# 02-DAC.net
KiCad netlist of a schematic drawn in Altium Designer
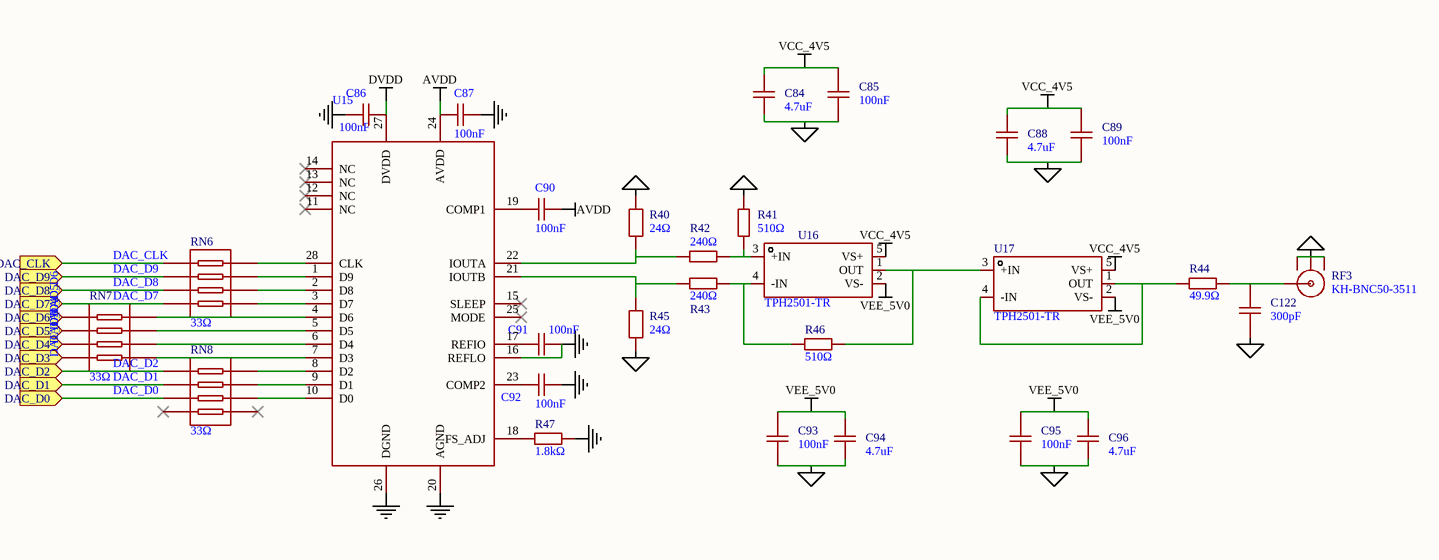
[diagram p0: 02-DAC.schdoc]

(export (version "E")
  (design (tool "Eeschema 10.0.6"))
  (components
    (comp (ref "C84")
      (value "4.7uF")
      (footprint "C0603")
      (fields
        (field (name "MANUFACTURER") "SAMSUNG(三星)")
        (field (name "MANUFACTURER PART") "CL10A475KO8NNNC")
        (field (name "TOLERANCE") "±10%")
      )
      (libsource (lib "altium-import") (part "root_1_CL10A475KO8NNNC_"))
    )
    (comp (ref "C85")
      (value "100nF")
      (footprint "C0603")
      (fields
        (field (name "MANUFACTURER") "HRE(芯声)")
        (field (name "MANUFACTURER PART") "CGA0603X7R104K500JT")
        (field (name "TOLERANCE") "±10%")
      )
      (libsource (lib "altium-import") (part "root_1_CGA0603X7R104K500JT_"))
    )
    (comp (ref "C86")
      (value "100nF")
      (footprint "C0603")
      (fields
        (field (name "MANUFACTURER") "HRE(芯声)")
        (field (name "MANUFACTURER PART") "CGA0603X7R104K500JT")
        (field (name "ALTIUM_VALUE") "100nF")
        (field (name "TOLERANCE") "±10%")
      )
      (libsource (lib "altium-import") (part "root_0_CGA0603X7R104K500JT_"))
    )
    (comp (ref "C87")
      (value "100nF")
      (footprint "C0603")
      (fields
        (field (name "MANUFACTURER") "HRE(芯声)")
        (field (name "MANUFACTURER PART") "CGA0603X7R104K500JT")
        (field (name "ALTIUM_VALUE") "100nF")
        (field (name "TOLERANCE") "±10%")
      )
      (libsource (lib "altium-import") (part "root_2_CGA0603X7R104K500JT_"))
    )
    (comp (ref "C88")
      (value "4.7uF")
      (footprint "C0603")
      (fields
        (field (name "MANUFACTURER") "SAMSUNG(三星)")
        (field (name "MANUFACTURER PART") "CL10A475KO8NNNC")
        (field (name "TOLERANCE") "±10%")
      )
      (libsource (lib "altium-import") (part "root_1_CL10A475KO8NNNC_"))
    )
    (comp (ref "C89")
      (value "100nF")
      (footprint "C0603")
      (fields
        (field (name "MANUFACTURER") "HRE(芯声)")
        (field (name "MANUFACTURER PART") "CGA0603X7R104K500JT")
        (field (name "TOLERANCE") "±10%")
      )
      (libsource (lib "altium-import") (part "root_1_CGA0603X7R104K500JT_"))
    )
    (comp (ref "C90")
      (value "100nF")
      (footprint "C0603")
      (fields
        (field (name "MANUFACTURER") "HRE(芯声)")
        (field (name "MANUFACTURER PART") "CGA0603X7R104K500JT")
        (field (name "ALTIUM_VALUE") "100nF")
        (field (name "TOLERANCE") "±10%")
      )
      (libsource (lib "altium-import") (part "root_2_CGA0603X7R104K500JT_"))
    )
    (comp (ref "C91")
      (value "100nF")
      (footprint "C0603")
      (fields
        (field (name "MANUFACTURER") "HRE(芯声)")
        (field (name "MANUFACTURER PART") "CGA0603X7R104K500JT")
        (field (name "ALTIUM_VALUE") "100nF")
        (field (name "TOLERANCE") "±10%")
      )
      (libsource (lib "altium-import") (part "root_2_CGA0603X7R104K500JT_"))
    )
    (comp (ref "C92")
      (value "100nF")
      (footprint "C0603")
      (fields
        (field (name "MANUFACTURER") "HRE(芯声)")
        (field (name "MANUFACTURER PART") "CGA0603X7R104K500JT")
        (field (name "ALTIUM_VALUE") "100nF")
        (field (name "TOLERANCE") "±10%")
      )
      (libsource (lib "altium-import") (part "root_2_CGA0603X7R104K500JT_"))
    )
    (comp (ref "C93")
      (value "100nF")
      (footprint "C0603")
      (fields
        (field (name "MANUFACTURER") "HRE(芯声)")
        (field (name "MANUFACTURER PART") "CGA0603X7R104K500JT")
        (field (name "TOLERANCE") "±10%")
      )
      (libsource (lib "altium-import") (part "root_1_CGA0603X7R104K500JT_"))
    )
    (comp (ref "C94")
      (value "4.7uF")
      (footprint "C0603")
      (fields
        (field (name "MANUFACTURER") "SAMSUNG(三星)")
        (field (name "MANUFACTURER PART") "CL10A475KO8NNNC")
        (field (name "TOLERANCE") "±10%")
      )
      (libsource (lib "altium-import") (part "root_1_CL10A475KO8NNNC_"))
    )
    (comp (ref "C95")
      (value "100nF")
      (footprint "C0603")
      (fields
        (field (name "MANUFACTURER") "HRE(芯声)")
        (field (name "MANUFACTURER PART") "CGA0603X7R104K500JT")
        (field (name "TOLERANCE") "±10%")
      )
      (libsource (lib "altium-import") (part "root_1_CGA0603X7R104K500JT_"))
    )
    (comp (ref "C96")
      (value "4.7uF")
      (footprint "C0603")
      (fields
        (field (name "MANUFACTURER") "SAMSUNG(三星)")
        (field (name "MANUFACTURER PART") "CL10A475KO8NNNC")
        (field (name "TOLERANCE") "±10%")
      )
      (libsource (lib "altium-import") (part "root_1_CL10A475KO8NNNC_"))
    )
    (comp (ref "C122")
      (value "300pF")
      (footprint "C0603")
      (fields
        (field (name "MANUFACTURER") "YAGEO(国巨)")
        (field (name "MANUFACTURER PART") "CC0603JRNPO9BN301")
        (field (name "TOLERANCE") "±5%")
      )
      (libsource (lib "altium-import") (part "root_1_CC0603JRNPO9BN301_"))
    )
    (comp (ref "R40")
      (value "24Ω")
      (footprint "R0603")
      (fields
        (field (name "MANUFACTURER") "FOJAN(富捷)")
        (field (name "MANUFACTURER PART") "FRC0603F24R0TS")
        (field (name "TOLERANCE") "±1%")
      )
      (libsource (lib "altium-import") (part "root_1_FRC0603F24R0TS_"))
    )
    (comp (ref "R41")
      (value "510Ω")
      (footprint "R0603")
      (fields
        (field (name "MANUFACTURER") "UNI-ROYAL(厚声)")
        (field (name "MANUFACTURER PART") "0603WAF5100T5E")
        (field (name "TOLERANCE") "±1%")
      )
      (libsource (lib "altium-import") (part "root_1_0603WAF5100T5E_"))
    )
    (comp (ref "R42")
      (value "240Ω")
      (footprint "R0603")
      (fields
        (field (name "MANUFACTURER") "UNI-ROYAL(厚声)")
        (field (name "MANUFACTURER PART") "0603WAF2400T5E")
        (field (name "TOLERANCE") "±1%")
      )
      (libsource (lib "altium-import") (part "root_0_0603WAF2400T5E_"))
    )
    (comp (ref "R43")
      (value "240Ω")
      (footprint "R0603")
      (fields
        (field (name "MANUFACTURER") "UNI-ROYAL(厚声)")
        (field (name "MANUFACTURER PART") "0603WAF2400T5E")
        (field (name "TOLERANCE") "±1%")
      )
      (libsource (lib "altium-import") (part "root_0_0603WAF2400T5E_"))
    )
    (comp (ref "R44")
      (value "49.9Ω")
      (footprint "R0603")
      (fields
        (field (name "MANUFACTURER") "UNI-ROYAL(厚声)")
        (field (name "MANUFACTURER PART") "0603WAF499JT5E")
        (field (name "TOLERANCE") "±1%")
      )
      (libsource (lib "altium-import") (part "root_0_0603WAF499JT5E_"))
    )
    (comp (ref "R45")
      (value "24Ω")
      (footprint "R0603")
      (fields
        (field (name "MANUFACTURER") "FOJAN(富捷)")
        (field (name "MANUFACTURER PART") "FRC0603F24R0TS")
        (field (name "TOLERANCE") "±1%")
      )
      (libsource (lib "altium-import") (part "root_1_FRC0603F24R0TS_"))
    )
    (comp (ref "R46")
      (value "510Ω")
      (footprint "R0603")
      (fields
        (field (name "MANUFACTURER") "UNI-ROYAL(厚声)")
        (field (name "MANUFACTURER PART") "0603WAF5100T5E")
        (field (name "TOLERANCE") "±1%")
      )
      (libsource (lib "altium-import") (part "root_0_0603WAF5100T5E_"))
    )
    (comp (ref "R47")
      (value "1.8kΩ")
      (footprint "R0603")
      (fields
        (field (name "MANUFACTURER") "UNI-ROYAL(厚声)")
        (field (name "MANUFACTURER PART") "0603WAF1801T5E")
        (field (name "TOLERANCE") "±1%")
      )
      (libsource (lib "altium-import") (part "root_0_0603WAF1801T5E_"))
    )
    (comp (ref "RF3")
      (value "KH-BNC50-3511")
      (footprint "ANT-TH_KH-BNC50-3511")
      (fields (field (name "MANUFACTURER") "kinghelm(金航标)"))
      (libsource (lib "altium-import") (part "root_2_KH-BNC50-3511_"))
    )
    (comp (ref "RN6")
      (value "33Ω")
      (footprint "RES-ARRAY-SMD_0603-8P-L3.2-W1.6-BL")
      (fields
        (field (name "MANUFACTURER") "UNI-ROYAL(厚声)")
        (field (name "MANUFACTURER PART") "4D03WGJ0330T5E")
        (field (name "TOLERANCE") "±5%")
      )
      (libsource (lib "altium-import") (part "root_2_4D03WGJ0330T5E_"))
    )
    (comp (ref "RN7")
      (value "33Ω")
      (footprint "RES-ARRAY-SMD_0603-8P-L3.2-W1.6-BL")
      (fields
        (field (name "MANUFACTURER") "UNI-ROYAL(厚声)")
        (field (name "MANUFACTURER PART") "4D03WGJ0330T5E")
        (field (name "TOLERANCE") "±5%")
      )
      (libsource (lib "altium-import") (part "root_0_4D03WGJ0330T5E_"))
    )
    (comp (ref "RN8")
      (value "33Ω")
      (footprint "RES-ARRAY-SMD_0603-8P-L3.2-W1.6-BL")
      (fields
        (field (name "MANUFACTURER") "UNI-ROYAL(厚声)")
        (field (name "MANUFACTURER PART") "4D03WGJ0330T5E")
        (field (name "TOLERANCE") "±5%")
      )
      (libsource (lib "altium-import") (part "root_0_4D03WGJ0330T5E_"))
    )
    (comp (ref "U15")
      (value "~")
      (footprint "TSSOP-28_L9.7-W4.4-P0.65-LS6.4-TR")
      (libsource (lib "altium-import") (part "root_0_3PD5651_"))
    )
    (comp (ref "U16")
      (value "TPH2501-TR")
      (footprint "SOT-23-5_L3.0-W1.7-P0.95-LS2.8-BR")
      (fields (field (name "MANUFACTURER") "3PEAK(思瑞浦)"))
      (libsource (lib "altium-import") (part "root_0_TPH2501-TR_"))
    )
    (comp (ref "U17")
      (value "TPH2501-TR")
      (footprint "SOT-23-5_L3.0-W1.7-P0.95-LS2.8-BR")
      (fields (field (name "MANUFACTURER") "3PEAK(思瑞浦)"))
      (libsource (lib "altium-import") (part "root_0_TPH2501-TR_"))
    )
  )
  (nets
    (net (code "1") (name "/DAC_CLK") (class "Default")
      (node (ref "RN6") (pin "5") (pinfunction "5_5") (pintype "passive"))
    )
    (net (code "2") (name "/DAC_D0") (class "Default")
      (node (ref "RN8") (pin "3") (pinfunction "3_3") (pintype "passive"))
    )
    (net (code "3") (name "/DAC_D1") (class "Default")
      (node (ref "RN8") (pin "2") (pinfunction "2_2") (pintype "passive"))
    )
    (net (code "4") (name "/DAC_D2") (class "Default")
      (node (ref "RN8") (pin "1") (pinfunction "1_1") (pintype "passive"))
    )
    (net (code "5") (name "/DAC_D3") (class "Default")
      (node (ref "RN7") (pin "4") (pinfunction "4_4") (pintype "passive"))
    )
    (net (code "6") (name "/DAC_D4") (class "Default")
      (node (ref "RN7") (pin "3") (pinfunction "3_3") (pintype "passive"))
    )
    (net (code "7") (name "/DAC_D5") (class "Default")
      (node (ref "RN7") (pin "2") (pinfunction "2_2") (pintype "passive"))
    )
    (net (code "8") (name "/DAC_D6") (class "Default")
      (node (ref "RN7") (pin "1") (pinfunction "1_1") (pintype "passive"))
    )
    (net (code "9") (name "/DAC_D7") (class "Default")
      (node (ref "RN6") (pin "8") (pinfunction "8_8") (pintype "passive"))
    )
    (net (code "10") (name "/DAC_D8") (class "Default")
      (node (ref "RN6") (pin "7") (pinfunction "7_7") (pintype "passive"))
    )
    (net (code "11") (name "/DAC_D9") (class "Default")
      (node (ref "RN6") (pin "6") (pinfunction "6_6") (pintype "passive"))
    )
    (net (code "12") (name "AGND") (class "Default")
      (node (ref "C122") (pin "1") (pinfunction "1_1") (pintype "passive"))
      (node (ref "C84") (pin "1") (pinfunction "1_1") (pintype "passive"))
      (node (ref "C85") (pin "1") (pinfunction "1_1") (pintype "passive"))
      (node (ref "C88") (pin "1") (pinfunction "1_1") (pintype "passive"))
      (node (ref "C89") (pin "1") (pinfunction "1_1") (pintype "passive"))
      (node (ref "C93") (pin "1") (pinfunction "1_1") (pintype "passive"))
      (node (ref "C94") (pin "1") (pinfunction "1_1") (pintype "passive"))
      (node (ref "C95") (pin "1") (pinfunction "1_1") (pintype "passive"))
      (node (ref "C96") (pin "1") (pinfunction "1_1") (pintype "passive"))
      (node (ref "R40") (pin "2") (pinfunction "2_2") (pintype "passive"))
      (node (ref "R41") (pin "2") (pinfunction "2_2") (pintype "passive"))
      (node (ref "R45") (pin "1") (pinfunction "1_1") (pintype "passive"))
      (node (ref "RF3") (pin "2") (pinfunction "2_2") (pintype "passive"))
      (node (ref "RF3") (pin "3") (pinfunction "3_3") (pintype "passive"))
      (node (ref "RF3") (pin "4") (pinfunction "4_4") (pintype "passive"))
    )
    (net (code "13") (name "AVDD") (class "Default")
      (node (ref "C87") (pin "2") (pinfunction "2_2") (pintype "passive"))
      (node (ref "C90") (pin "1") (pinfunction "1_1") (pintype "passive"))
      (node (ref "U15") (pin "24") (pinfunction "AVDD_24") (pintype "passive"))
    )
    (net (code "14") (name "DVDD") (class "Default")
      (node (ref "C86") (pin "2") (pinfunction "2_2") (pintype "passive"))
      (node (ref "U15") (pin "27") (pinfunction "DVDD_27") (pintype "passive"))
    )
    (net (code "15") (name "GND") (class "Default")
      (node (ref "C86") (pin "1") (pinfunction "1_1") (pintype "passive"))
      (node (ref "C87") (pin "1") (pinfunction "1_1") (pintype "passive"))
      (node (ref "C91") (pin "1") (pinfunction "1_1") (pintype "passive"))
      (node (ref "C92") (pin "1") (pinfunction "1_1") (pintype "passive"))
      (node (ref "R47") (pin "2") (pinfunction "2_2") (pintype "passive"))
      (node (ref "U15") (pin "16") (pinfunction "REFLO_16") (pintype "passive"))
      (node (ref "U15") (pin "20") (pinfunction "AGND_20") (pintype "passive"))
      (node (ref "U15") (pin "26") (pinfunction "DGND_26") (pintype "passive"))
    )
    (net (code "16") (name "Net-(RF3-OUT)") (class "Default")
      (node (ref "C122") (pin "2") (pinfunction "2_2") (pintype "passive"))
      (node (ref "R44") (pin "2") (pinfunction "2_2") (pintype "passive"))
      (node (ref "RF3") (pin "1") (pinfunction "OUT_1") (pintype "passive"))
    )
    (net (code "17") (name "Net-(U15-CLK)") (class "Default")
      (node (ref "RN6") (pin "4") (pinfunction "4_4") (pintype "passive"))
      (node (ref "U15") (pin "28") (pinfunction "CLK_28") (pintype "passive"))
    )
    (net (code "18") (name "Net-(U15-COMP1)") (class "Default")
      (node (ref "C90") (pin "2") (pinfunction "2_2") (pintype "passive"))
      (node (ref "U15") (pin "19") (pinfunction "COMP1_19") (pintype "passive"))
    )
    (net (code "19") (name "Net-(U15-COMP2)") (class "Default")
      (node (ref "C92") (pin "2") (pinfunction "2_2") (pintype "passive"))
      (node (ref "U15") (pin "23") (pinfunction "COMP2_23") (pintype "passive"))
    )
    (net (code "20") (name "Net-(U15-D0)") (class "Default")
      (node (ref "RN8") (pin "6") (pinfunction "6_6") (pintype "passive"))
      (node (ref "U15") (pin "10") (pinfunction "D0_10") (pintype "passive"))
    )
    (net (code "21") (name "Net-(U15-D1)") (class "Default")
      (node (ref "RN8") (pin "7") (pinfunction "7_7") (pintype "passive"))
      (node (ref "U15") (pin "9") (pinfunction "D1_9") (pintype "passive"))
    )
    (net (code "22") (name "Net-(U15-D2)") (class "Default")
      (node (ref "RN8") (pin "8") (pinfunction "8_8") (pintype "passive"))
      (node (ref "U15") (pin "8") (pinfunction "D2_8") (pintype "passive"))
    )
    (net (code "23") (name "Net-(U15-D3)") (class "Default")
      (node (ref "RN7") (pin "5") (pinfunction "5_5") (pintype "passive"))
      (node (ref "U15") (pin "7") (pinfunction "D3_7") (pintype "passive"))
    )
    (net (code "24") (name "Net-(U15-D4)") (class "Default")
      (node (ref "RN7") (pin "6") (pinfunction "6_6") (pintype "passive"))
      (node (ref "U15") (pin "6") (pinfunction "D4_6") (pintype "passive"))
    )
    (net (code "25") (name "Net-(U15-D5)") (class "Default")
      (node (ref "RN7") (pin "7") (pinfunction "7_7") (pintype "passive"))
      (node (ref "U15") (pin "5") (pinfunction "D5_5") (pintype "passive"))
    )
    (net (code "26") (name "Net-(U15-D6)") (class "Default")
      (node (ref "RN7") (pin "8") (pinfunction "8_8") (pintype "passive"))
      (node (ref "U15") (pin "4") (pinfunction "D6_4") (pintype "passive"))
    )
    (net (code "27") (name "Net-(U15-D7)") (class "Default")
      (node (ref "RN6") (pin "1") (pinfunction "1_1") (pintype "passive"))
      (node (ref "U15") (pin "3") (pinfunction "D7_3") (pintype "passive"))
    )
    (net (code "28") (name "Net-(U15-D8)") (class "Default")
      (node (ref "RN6") (pin "2") (pinfunction "2_2") (pintype "passive"))
      (node (ref "U15") (pin "2") (pinfunction "D8_2") (pintype "passive"))
    )
    (net (code "29") (name "Net-(U15-D9)") (class "Default")
      (node (ref "RN6") (pin "3") (pinfunction "3_3") (pintype "passive"))
      (node (ref "U15") (pin "1") (pinfunction "D9_1") (pintype "passive"))
    )
    (net (code "30") (name "Net-(U15-FS_ADJ)") (class "Default")
      (node (ref "R47") (pin "1") (pinfunction "1_1") (pintype "passive"))
      (node (ref "U15") (pin "18") (pinfunction "FS_ADJ_18") (pintype "passive"))
    )
    (net (code "31") (name "Net-(U15-IOUTA)") (class "Default")
      (node (ref "R40") (pin "1") (pinfunction "1_1") (pintype "passive"))
      (node (ref "R42") (pin "1") (pinfunction "1_1") (pintype "passive"))
      (node (ref "U15") (pin "22") (pinfunction "IOUTA_22") (pintype "passive"))
    )
    (net (code "32") (name "Net-(U15-IOUTB)") (class "Default")
      (node (ref "R43") (pin "1") (pinfunction "1_1") (pintype "passive"))
      (node (ref "R45") (pin "2") (pinfunction "2_2") (pintype "passive"))
      (node (ref "U15") (pin "21") (pinfunction "IOUTB_21") (pintype "passive"))
    )
    (net (code "33") (name "Net-(U15-REFIO)") (class "Default")
      (node (ref "C91") (pin "2") (pinfunction "2_2") (pintype "passive"))
      (node (ref "U15") (pin "17") (pinfunction "REFIO_17") (pintype "passive"))
    )
    (net (code "34") (name "Net-(U16-+IN)") (class "Default")
      (node (ref "R41") (pin "1") (pinfunction "1_1") (pintype "passive"))
      (node (ref "R42") (pin "2") (pinfunction "2_2") (pintype "passive"))
      (node (ref "U16") (pin "3") (pinfunction "+IN_3") (pintype "passive"))
    )
    (net (code "35") (name "Net-(U16--IN)") (class "Default")
      (node (ref "R43") (pin "2") (pinfunction "2_2") (pintype "passive"))
      (node (ref "R46") (pin "1") (pinfunction "1_1") (pintype "passive"))
      (node (ref "U16") (pin "4") (pinfunction "-IN_4") (pintype "passive"))
    )
    (net (code "36") (name "Net-(U16-OUT)") (class "Default")
      (node (ref "R46") (pin "2") (pinfunction "2_2") (pintype "passive"))
      (node (ref "U16") (pin "1") (pinfunction "OUT_1") (pintype "passive"))
      (node (ref "U17") (pin "3") (pinfunction "+IN_3") (pintype "passive"))
    )
    (net (code "37") (name "Net-(U17--IN)") (class "Default")
      (node (ref "R44") (pin "1") (pinfunction "1_1") (pintype "passive"))
      (node (ref "U17") (pin "1") (pinfunction "OUT_1") (pintype "passive"))
      (node (ref "U17") (pin "4") (pinfunction "-IN_4") (pintype "passive"))
    )
    (net (code "38") (name "VCC_4V5") (class "Default")
      (node (ref "C84") (pin "2") (pinfunction "2_2") (pintype "passive"))
      (node (ref "C85") (pin "2") (pinfunction "2_2") (pintype "passive"))
      (node (ref "C88") (pin "2") (pinfunction "2_2") (pintype "passive"))
      (node (ref "C89") (pin "2") (pinfunction "2_2") (pintype "passive"))
      (node (ref "U16") (pin "5") (pinfunction "VS+_5") (pintype "passive"))
      (node (ref "U17") (pin "5") (pinfunction "VS+_5") (pintype "passive"))
    )
    (net (code "39") (name "VEE_5V0") (class "Default")
      (node (ref "C93") (pin "2") (pinfunction "2_2") (pintype "passive"))
      (node (ref "C94") (pin "2") (pinfunction "2_2") (pintype "passive"))
      (node (ref "C95") (pin "2") (pinfunction "2_2") (pintype "passive"))
      (node (ref "C96") (pin "2") (pinfunction "2_2") (pintype "passive"))
      (node (ref "U16") (pin "2") (pinfunction "VS-_2") (pintype "passive"))
      (node (ref "U17") (pin "2") (pinfunction "VS-_2") (pintype "passive"))
    )
    (net (code "40") (name "unconnected-(RN8-Pad4)") (class "Default")
      (node (ref "RN8") (pin "4") (pinfunction "4_4") (pintype "passive+no_connect"))
    )
    (net (code "41") (name "unconnected-(RN8-Pad5)") (class "Default")
      (node (ref "RN8") (pin "5") (pinfunction "5_5") (pintype "passive+no_connect"))
    )
    (net (code "42") (name "unconnected-(U15-MODE-Pad25)") (class "Default")
      (node (ref "U15") (pin "25") (pinfunction "MODE_25") (pintype "passive+no_connect"))
    )
    (net (code "43") (name "unconnected-(U15-NC-Pad11)") (class "Default")
      (node (ref "U15") (pin "11") (pinfunction "NC_11") (pintype "passive+no_connect"))
    )
    (net (code "44") (name "unconnected-(U15-NC-Pad12)") (class "Default")
      (node (ref "U15") (pin "12") (pinfunction "NC_12") (pintype "passive+no_connect"))
    )
    (net (code "45") (name "unconnected-(U15-NC-Pad13)") (class "Default")
      (node (ref "U15") (pin "13") (pinfunction "NC_13") (pintype "passive+no_connect"))
    )
    (net (code "46") (name "unconnected-(U15-NC-Pad14)") (class "Default")
      (node (ref "U15") (pin "14") (pinfunction "NC_14") (pintype "passive+no_connect"))
    )
    (net (code "47") (name "unconnected-(U15-SLEEP-Pad15)") (class "Default")
      (node (ref "U15") (pin "15") (pinfunction "SLEEP_15") (pintype "passive+no_connect"))
    )
  )
)
